# Root_ESP_v1_0.net
KiCad netlist of a schematic drawn in EAGLE
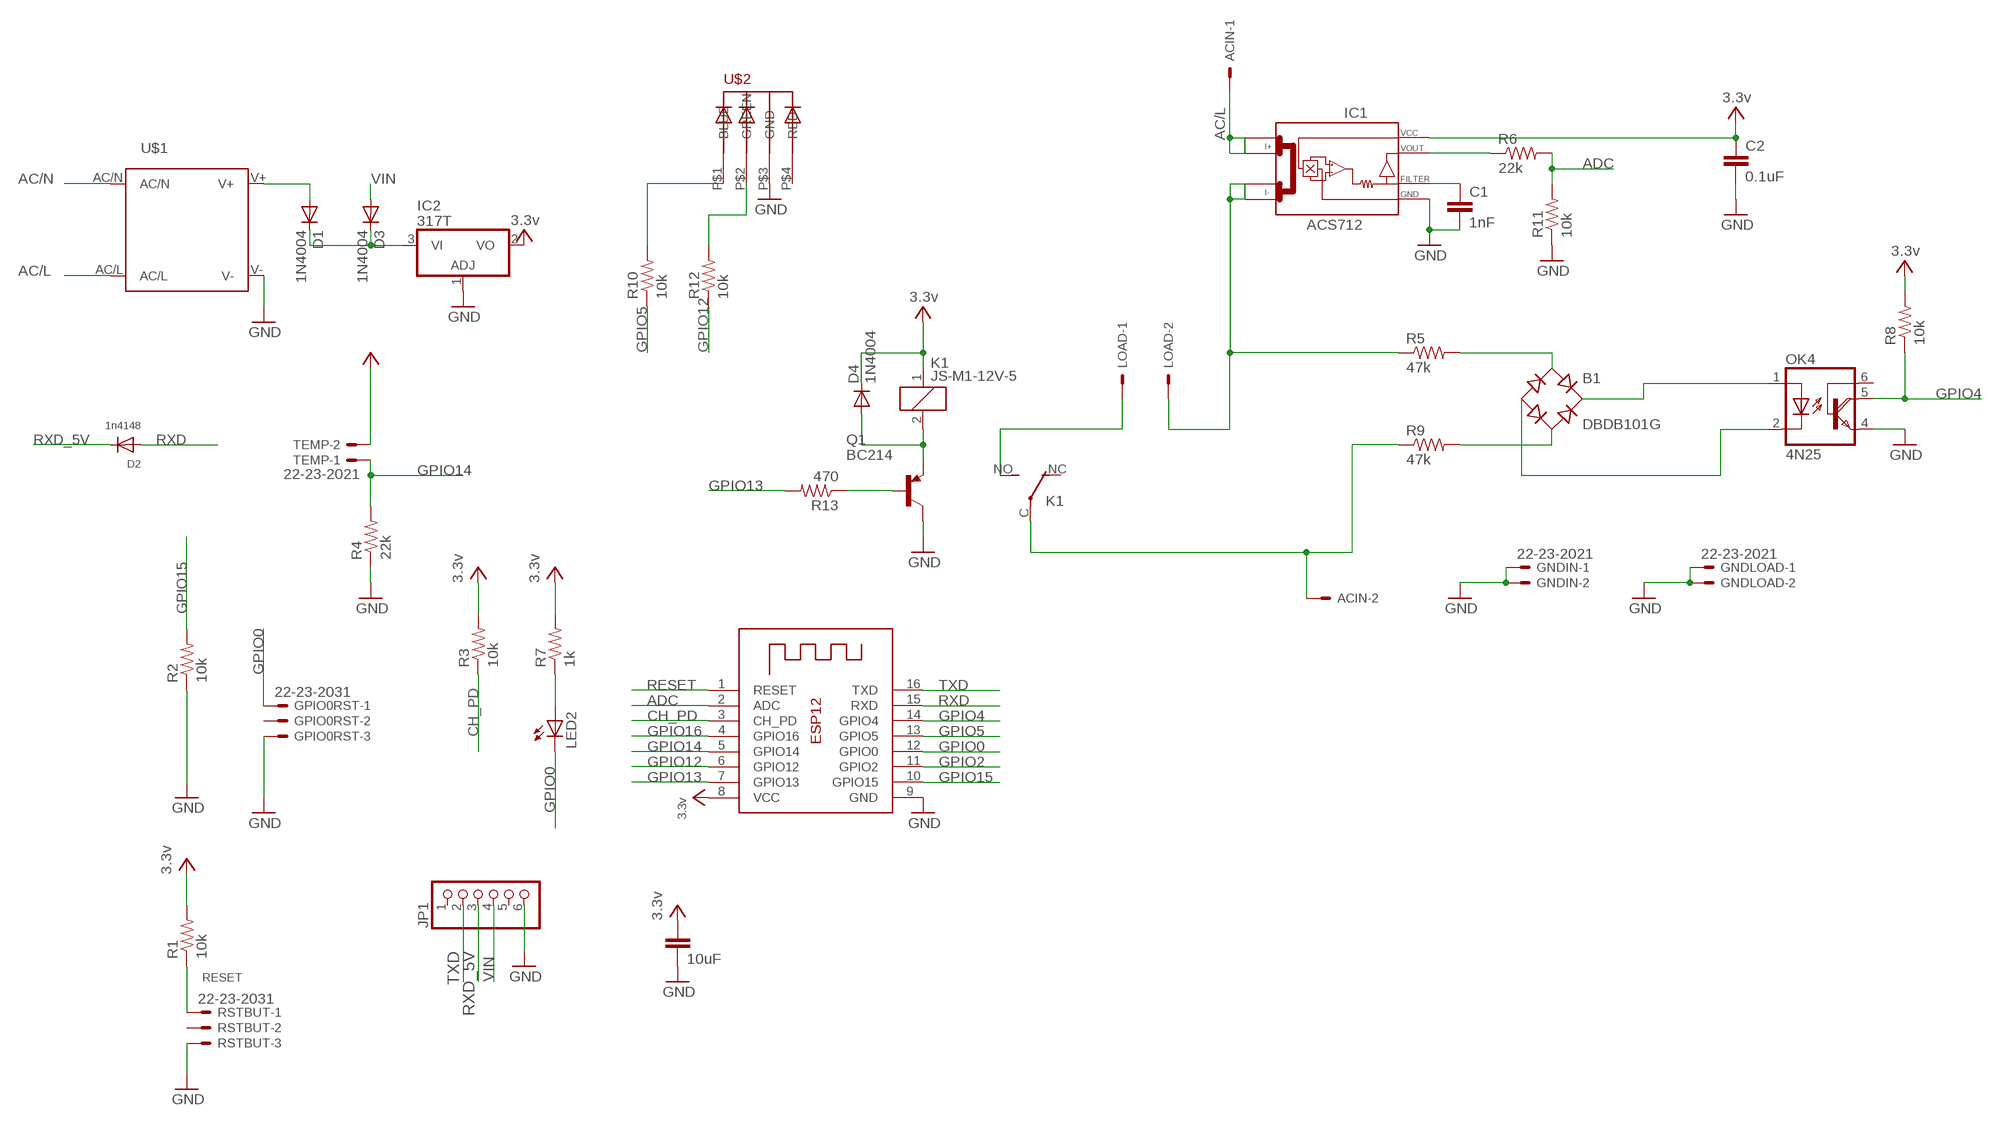
[diagram p0: schematic, sheet 1]

(export (version "E")
  (design (tool "Eeschema 10.0.6"))
  (components
    (comp (ref "ACIN")
      (value "22-23-2021")
      (footprint "eagle-import:22-23-2021")
      (fields (field (name "MF") "MOLEX"))
      (libsource (lib "eagle-import") (part "22-23-2021"))
    )
    (comp (ref "B1")
      (value "DBDB101G")
      (footprint "eagle-import:DB")
      (libsource (lib "eagle-import") (part "DB?GDB101"))
    )
    (comp (ref "C1")
      (value "1nF")
      (footprint "eagle-import:C5B2.5")
      (libsource (lib "eagle-import") (part "C5/2.5"))
    )
    (comp (ref "C2")
      (value "0.1uF")
      (footprint "eagle-import:C5B2.5")
      (libsource (lib "eagle-import") (part "C5/2.5"))
    )
    (comp (ref "C3")
      (value "10uF")
      (footprint "eagle-import:C5B3")
      (fields (field (name "C5") "0.1uF"))
      (libsource (lib "eagle-import") (part "C5/3"))
    )
    (comp (ref "D1")
      (value "1N4004")
      (footprint "eagle-import:DO41-10")
      (libsource (lib "eagle-import") (part "1N4004"))
    )
    (comp (ref "D2")
      (value "1n4148")
      (footprint "eagle-import:DO-1N4148")
      (libsource (lib "eagle-import") (part "DIODEDO-1N4148"))
    )
    (comp (ref "D3")
      (value "1N4004")
      (footprint "eagle-import:DO41-10")
      (libsource (lib "eagle-import") (part "1N4004"))
    )
    (comp (ref "D4")
      (value "1N4004")
      (footprint "eagle-import:DO41-10")
      (libsource (lib "eagle-import") (part "1N4004"))
    )
    (comp (ref "GNDIN")
      (value "22-23-2021")
      (footprint "eagle-import:22-23-2021")
      (fields (field (name "MF") "MOLEX"))
      (libsource (lib "eagle-import") (part "22-23-2021"))
    )
    (comp (ref "GNDLOAD")
      (value "22-23-2021")
      (footprint "eagle-import:22-23-2021")
      (fields (field (name "MF") "MOLEX"))
      (libsource (lib "eagle-import") (part "22-23-2021"))
    )
    (comp (ref "GPIO0RST")
      (value "22-23-2031")
      (footprint "eagle-import:22-23-2031")
      (fields (field (name "MF") "MOLEX"))
      (libsource (lib "eagle-import") (part "22-23-2031"))
    )
    (comp (ref "IC1")
      (value "ACS712")
      (footprint "eagle-import:SO08")
      (libsource (lib "eagle-import") (part "ACS712"))
    )
    (comp (ref "IC2")
      (value "317T")
      (footprint "eagle-import:TO220H")
      (libsource (lib "eagle-import") (part "317T"))
    )
    (comp (ref "JP1")
      (value "PINHD-1X6-3.5MM")
      (footprint "eagle-import:1X06-3.5MM")
      (libsource (lib "eagle-import") (part "PINHD-1X6-3.5MM"))
    )
    (comp (ref "K1")
      (value "JS-M1-12V-5")
      (footprint "eagle-import:JS-M")
      (fields (field (name "MF") "FARNELL") (field (name "MPN") "JSM1-12V-5"))
      (libsource (lib "eagle-import") (part "JS-M1-12V-5"))
    )
    (comp (ref "LED2")
      (value "LED5MM")
      (footprint "eagle-import:LED5MM")
      (libsource (lib "eagle-import") (part "LED5MM"))
    )
    (comp (ref "LOAD")
      (value "22-23-2021")
      (footprint "eagle-import:22-23-2021")
      (fields (field (name "MF") "MOLEX"))
      (libsource (lib "eagle-import") (part "22-23-2021"))
    )
    (comp (ref "OK4")
      (value "4N25")
      (footprint "eagle-import:DIL06")
      (libsource (lib "eagle-import") (part "4N25"))
    )
    (comp (ref "Q1")
      (value "BC214")
      (footprint "eagle-import:TO92")
      (libsource (lib "eagle-import") (part "BC214"))
    )
    (comp (ref "R1")
      (value "10k")
      (footprint "eagle-import:0204_7")
      (libsource (lib "eagle-import") (part "R-US_0204/7"))
    )
    (comp (ref "R2")
      (value "10k")
      (footprint "eagle-import:0204_7")
      (libsource (lib "eagle-import") (part "R-US_0204/7"))
    )
    (comp (ref "R3")
      (value "10k")
      (footprint "eagle-import:0204_7")
      (libsource (lib "eagle-import") (part "R-US_0204/7"))
    )
    (comp (ref "R4")
      (value "22k")
      (footprint "eagle-import:0204_7")
      (libsource (lib "eagle-import") (part "R-US_0204/7"))
    )
    (comp (ref "R5")
      (value "47k")
      (footprint "eagle-import:0204_7")
      (libsource (lib "eagle-import") (part "R-US_0204/7"))
    )
    (comp (ref "R6")
      (value "22k")
      (footprint "eagle-import:0204_7")
      (libsource (lib "eagle-import") (part "R-US_0204/7"))
    )
    (comp (ref "R7")
      (value "1k")
      (footprint "eagle-import:0204_7")
      (libsource (lib "eagle-import") (part "R-US_0204/7"))
    )
    (comp (ref "R8")
      (value "10k")
      (footprint "eagle-import:0204_7")
      (libsource (lib "eagle-import") (part "R-US_0204/7"))
    )
    (comp (ref "R9")
      (value "47k")
      (footprint "eagle-import:0204_7")
      (libsource (lib "eagle-import") (part "R-US_0204/7"))
    )
    (comp (ref "R10")
      (value "10k")
      (footprint "eagle-import:0204_7")
      (libsource (lib "eagle-import") (part "R-US_0204/7"))
    )
    (comp (ref "R11")
      (value "10k")
      (footprint "eagle-import:0204_7")
      (libsource (lib "eagle-import") (part "R-US_0204/7"))
    )
    (comp (ref "R12")
      (value "10k")
      (footprint "eagle-import:0204_7")
      (libsource (lib "eagle-import") (part "R-US_0204/7"))
    )
    (comp (ref "R13")
      (value "470")
      (footprint "eagle-import:0204_7")
      (libsource (lib "eagle-import") (part "R-US_0204/7"))
    )
    (comp (ref "RSTBUT")
      (value "22-23-2031")
      (footprint "eagle-import:22-23-2031")
      (fields (field (name "MF") "MOLEX"))
      (libsource (lib "eagle-import") (part "22-23-2031"))
    )
    (comp (ref "TEMP")
      (value "22-23-2021")
      (footprint "eagle-import:22-23-2021")
      (fields (field (name "MF") "MOLEX"))
      (libsource (lib "eagle-import") (part "22-23-2021"))
    )
    (comp (ref "U$1")
      (value "IRM_03IRM_03")
      (footprint "eagle-import:IRM_03")
      (libsource (lib "eagle-import") (part "IRM_03IRM_03"))
    )
    (comp (ref "U$2")
      (value "5MMRGBLED")
      (footprint "eagle-import:LED5MMRGB")
      (libsource (lib "eagle-import") (part "5MMRGBLED"))
    )
    (comp (ref "X1")
      (value "ESP-12")
      (footprint "eagle-import:ESP-12")
      (libsource (lib "eagle-import") (part "ESP-12"))
    )
  )
  (nets
    (net (code "1") (name "/AC{slash}L") (class "Default")
      (node (ref "ACIN") (pin "1") (pinfunction "S_1") (pintype "passive"))
      (node (ref "IC1") (pin "1") (pinfunction "I+_0_1") (pintype "bidirectional"))
      (node (ref "IC1") (pin "2") (pinfunction "I+_1_2") (pintype "bidirectional"))
      (node (ref "U$1") (pin "AC/L") (pinfunction "AC/L_AC/L") (pintype "input"))
    )
    (net (code "2") (name "/AC{slash}N") (class "Default")
      (node (ref "ACIN") (pin "2") (pinfunction "S_2") (pintype "passive"))
      (node (ref "K1") (pin "C") (pinfunction "P_C") (pintype "passive"))
      (node (ref "R9") (pin "1") (pinfunction "1_1") (pintype "passive"))
      (node (ref "U$1") (pin "AC/N") (pinfunction "AC/N_AC/N") (pintype "input"))
    )
    (net (code "3") (name "/ADC") (class "Default")
      (node (ref "R11") (pin "2") (pinfunction "2_2") (pintype "passive"))
      (node (ref "R6") (pin "2") (pinfunction "2_2") (pintype "passive"))
      (node (ref "X1") (pin "2") (pinfunction "ADC_2") (pintype "passive"))
    )
    (net (code "4") (name "/CH_PD") (class "Default")
      (node (ref "R3") (pin "1") (pinfunction "1_1") (pintype "passive"))
      (node (ref "X1") (pin "3") (pinfunction "CH_PD_3") (pintype "input"))
    )
    (net (code "5") (name "/GPIO0") (class "Default")
      (node (ref "GPIO0RST") (pin "1") (pinfunction "S_1") (pintype "passive"))
      (node (ref "LED2") (pin "K") (pinfunction "C_K") (pintype "passive"))
      (node (ref "X1") (pin "12") (pinfunction "GPIO0_12") (pintype "bidirectional"))
    )
    (net (code "6") (name "/GPIO2") (class "Default")
      (node (ref "X1") (pin "11") (pinfunction "GPIO2_11") (pintype "bidirectional"))
    )
    (net (code "7") (name "/GPIO4") (class "Default")
      (node (ref "OK4") (pin "5") (pinfunction "COL_5") (pintype "passive"))
      (node (ref "R8") (pin "1") (pinfunction "1_1") (pintype "passive"))
      (node (ref "X1") (pin "14") (pinfunction "GPIO4_14") (pintype "bidirectional"))
    )
    (net (code "8") (name "/GPIO5") (class "Default")
      (node (ref "R10") (pin "1") (pinfunction "1_1") (pintype "passive"))
      (node (ref "X1") (pin "13") (pinfunction "GPIO5_13") (pintype "bidirectional"))
    )
    (net (code "9") (name "/GPIO12") (class "Default")
      (node (ref "R12") (pin "1") (pinfunction "1_1") (pintype "passive"))
      (node (ref "X1") (pin "6") (pinfunction "GPIO12_6") (pintype "bidirectional"))
    )
    (net (code "10") (name "/GPIO13") (class "Default")
      (node (ref "R13") (pin "2") (pinfunction "2_2") (pintype "passive"))
      (node (ref "X1") (pin "7") (pinfunction "GPIO13_7") (pintype "bidirectional"))
    )
    (net (code "11") (name "/GPIO14") (class "Default")
      (node (ref "R4") (pin "2") (pinfunction "2_2") (pintype "passive"))
      (node (ref "TEMP") (pin "1") (pinfunction "S_1") (pintype "passive"))
      (node (ref "X1") (pin "5") (pinfunction "GPIO14_5") (pintype "bidirectional"))
    )
    (net (code "12") (name "/GPIO15") (class "Default")
      (node (ref "R2") (pin "2") (pinfunction "2_2") (pintype "passive"))
      (node (ref "X1") (pin "10") (pinfunction "GPIO15_10") (pintype "bidirectional"))
    )
    (net (code "13") (name "/GPIO16") (class "Default")
      (node (ref "X1") (pin "4") (pinfunction "GPIO16_4") (pintype "bidirectional"))
    )
    (net (code "14") (name "/RESET") (class "Default")
      (node (ref "R1") (pin "1") (pinfunction "1_1") (pintype "passive"))
      (node (ref "RSTBUT") (pin "1") (pinfunction "S_1") (pintype "passive"))
      (node (ref "X1") (pin "1") (pinfunction "RESET_1") (pintype "input"))
    )
    (net (code "15") (name "/RXD") (class "Default")
      (node (ref "D2") (pin "A") (pinfunction "A_A") (pintype "passive"))
      (node (ref "X1") (pin "15") (pinfunction "RXD_15") (pintype "input"))
    )
    (net (code "16") (name "/RXD_5V") (class "Default")
      (node (ref "D2") (pin "C") (pinfunction "C_C") (pintype "passive"))
      (node (ref "JP1") (pin "3") (pinfunction "3_3") (pintype "passive"))
    )
    (net (code "17") (name "/TXD") (class "Default")
      (node (ref "JP1") (pin "2") (pinfunction "2_2") (pintype "passive"))
      (node (ref "X1") (pin "16") (pinfunction "TXD_16") (pintype "output"))
    )
    (net (code "18") (name "/VIN") (class "Default")
      (node (ref "D3") (pin "A") (pinfunction "A_A") (pintype "passive"))
      (node (ref "JP1") (pin "4") (pinfunction "4_4") (pintype "passive"))
    )
    (net (code "19") (name "3.3v") (class "Default")
      (node (ref "C2") (pin "1") (pinfunction "1_1") (pintype "passive"))
      (node (ref "C3") (pin "1") (pinfunction "1_1") (pintype "passive"))
      (node (ref "D4") (pin "C") (pinfunction "C_C") (pintype "passive"))
      (node (ref "IC1") (pin "8") (pinfunction "VCC_8") (pintype "power_in"))
      (node (ref "IC2") (pin "2") (pinfunction "VO_2") (pintype "passive"))
      (node (ref "K1") (pin "1") (pinfunction "1_1") (pintype "passive"))
      (node (ref "R1") (pin "2") (pinfunction "2_2") (pintype "passive"))
      (node (ref "R3") (pin "2") (pinfunction "2_2") (pintype "passive"))
      (node (ref "R7") (pin "2") (pinfunction "2_2") (pintype "passive"))
      (node (ref "R8") (pin "2") (pinfunction "2_2") (pintype "passive"))
      (node (ref "TEMP") (pin "2") (pinfunction "S_2") (pintype "passive"))
      (node (ref "X1") (pin "8") (pinfunction "VCC_8") (pintype "power_in"))
    )
    (net (code "20") (name "GND") (class "Default")
      (node (ref "C1") (pin "2") (pinfunction "2_2") (pintype "passive"))
      (node (ref "C2") (pin "2") (pinfunction "2_2") (pintype "passive"))
      (node (ref "C3") (pin "2") (pinfunction "2_2") (pintype "passive"))
      (node (ref "GNDIN") (pin "1") (pinfunction "S_1") (pintype "passive"))
      (node (ref "GNDIN") (pin "2") (pinfunction "S_2") (pintype "passive"))
      (node (ref "GNDLOAD") (pin "1") (pinfunction "S_1") (pintype "passive"))
      (node (ref "GNDLOAD") (pin "2") (pinfunction "S_2") (pintype "passive"))
      (node (ref "GPIO0RST") (pin "3") (pinfunction "S_3") (pintype "passive"))
      (node (ref "IC1") (pin "5") (pinfunction "GND_5") (pintype "power_in"))
      (node (ref "IC2") (pin "1") (pinfunction "ADJ_1") (pintype "input"))
      (node (ref "JP1") (pin "6") (pinfunction "6_6") (pintype "passive"))
      (node (ref "OK4") (pin "4") (pinfunction "E_4") (pintype "passive"))
      (node (ref "Q1") (pin "3") (pinfunction "C_3") (pintype "passive"))
      (node (ref "R11") (pin "1") (pinfunction "1_1") (pintype "passive"))
      (node (ref "R2") (pin "1") (pinfunction "1_1") (pintype "passive"))
      (node (ref "R4") (pin "1") (pinfunction "1_1") (pintype "passive"))
      (node (ref "RSTBUT") (pin "3") (pinfunction "S_3") (pintype "passive"))
      (node (ref "U$1") (pin "V-") (pinfunction "V-_V-") (pintype "output"))
      (node (ref "U$2") (pin "P$3") (pinfunction "GND_P$3") (pintype "bidirectional"))
      (node (ref "X1") (pin "9") (pinfunction "GND_9") (pintype "power_in"))
    )
    (net (code "21") (name "Net-(B1-PadAC1)") (class "Default")
      (node (ref "B1") (pin "AC1") (pinfunction "AC1_AC1") (pintype "passive"))
      (node (ref "R5") (pin "2") (pinfunction "2_2") (pintype "passive"))
    )
    (net (code "22") (name "Net-(B1-PadAC2)") (class "Default")
      (node (ref "B1") (pin "AC2") (pinfunction "AC2_AC2") (pintype "passive"))
      (node (ref "R9") (pin "2") (pinfunction "2_2") (pintype "passive"))
    )
    (net (code "23") (name "Net-(D1-PadA)") (class "Default")
      (node (ref "D1") (pin "A") (pinfunction "A_A") (pintype "passive"))
      (node (ref "U$1") (pin "V+") (pinfunction "V+_V+") (pintype "output"))
    )
    (net (code "24") (name "Net-(IC1-FILTER)") (class "Default")
      (node (ref "C1") (pin "1") (pinfunction "1_1") (pintype "passive"))
      (node (ref "IC1") (pin "6") (pinfunction "FILTER_6") (pintype "bidirectional"))
    )
    (net (code "25") (name "Net-(IC1-I-_0)") (class "Default")
      (node (ref "IC1") (pin "3") (pinfunction "I-_0_3") (pintype "bidirectional"))
      (node (ref "IC1") (pin "4") (pinfunction "I-_1_4") (pintype "bidirectional"))
      (node (ref "LOAD") (pin "2") (pinfunction "S_2") (pintype "passive"))
      (node (ref "R5") (pin "1") (pinfunction "1_1") (pintype "passive"))
    )
    (net (code "26") (name "Net-(IC1-VOUT)") (class "Default")
      (node (ref "IC1") (pin "7") (pinfunction "VOUT_7") (pintype "output"))
      (node (ref "R6") (pin "1") (pinfunction "1_1") (pintype "passive"))
    )
    (net (code "27") (name "Net-(IC2-VI)") (class "Default")
      (node (ref "D1") (pin "C") (pinfunction "C_C") (pintype "passive"))
      (node (ref "D3") (pin "C") (pinfunction "C_C") (pintype "passive"))
      (node (ref "IC2") (pin "3") (pinfunction "VI_3") (pintype "input"))
    )
    (net (code "28") (name "Net-(K1B-S)") (class "Default")
      (node (ref "K1") (pin "NO") (pinfunction "S_NO") (pintype "passive"))
      (node (ref "LOAD") (pin "1") (pinfunction "S_1") (pintype "passive"))
    )
    (net (code "29") (name "Net-(LED2-PadA)") (class "Default")
      (node (ref "LED2") (pin "A") (pinfunction "A_A") (pintype "passive"))
      (node (ref "R7") (pin "1") (pinfunction "1_1") (pintype "passive"))
    )
    (net (code "30") (name "Net-(OK4-A)") (class "Default")
      (node (ref "B1") (pin "+") (pinfunction "+_+") (pintype "passive"))
      (node (ref "OK4") (pin "1") (pinfunction "A_1") (pintype "passive"))
    )
    (net (code "31") (name "Net-(OK4-C)") (class "Default")
      (node (ref "B1") (pin "-") (pinfunction "-_-") (pintype "passive"))
      (node (ref "OK4") (pin "2") (pinfunction "C_2") (pintype "passive"))
    )
    (net (code "32") (name "Net-(Q1-B)") (class "Default")
      (node (ref "Q1") (pin "2") (pinfunction "B_2") (pintype "passive"))
      (node (ref "R13") (pin "1") (pinfunction "1_1") (pintype "passive"))
    )
    (net (code "33") (name "Net-(Q1-E)") (class "Default")
      (node (ref "D4") (pin "A") (pinfunction "A_A") (pintype "passive"))
      (node (ref "K1") (pin "2") (pinfunction "2_2") (pintype "passive"))
      (node (ref "Q1") (pin "1") (pinfunction "E_1") (pintype "passive"))
    )
    (net (code "34") (name "Net-(U$2-BLUE)") (class "Default")
      (node (ref "R10") (pin "2") (pinfunction "2_2") (pintype "passive"))
      (node (ref "U$2") (pin "P$1") (pinfunction "BLUE_P$1") (pintype "bidirectional"))
    )
    (net (code "35") (name "Net-(U$2-GREEN)") (class "Default")
      (node (ref "R12") (pin "2") (pinfunction "2_2") (pintype "passive"))
      (node (ref "U$2") (pin "P$2") (pinfunction "GREEN_P$2") (pintype "bidirectional"))
    )
    (net (code "36") (name "unconnected-(GPIO0RSTB-S-Pad2)") (class "Default")
      (node (ref "GPIO0RST") (pin "2") (pinfunction "S_2") (pintype "passive"))
    )
    (net (code "37") (name "unconnected-(JP1-Pad1)") (class "Default")
      (node (ref "JP1") (pin "1") (pinfunction "1_1") (pintype "passive"))
    )
    (net (code "38") (name "unconnected-(JP1-Pad5)") (class "Default")
      (node (ref "JP1") (pin "5") (pinfunction "5_5") (pintype "passive"))
    )
    (net (code "39") (name "unconnected-(K1B-O-PadNC)") (class "Default")
      (node (ref "K1") (pin "NC") (pinfunction "O_NC") (pintype "passive"))
    )
    (net (code "40") (name "unconnected-(OK4-B-Pad6)") (class "Default")
      (node (ref "OK4") (pin "6") (pinfunction "B_6") (pintype "passive"))
    )
    (net (code "41") (name "unconnected-(RSTBUTB-S-Pad2)") (class "Default")
      (node (ref "RSTBUT") (pin "2") (pinfunction "S_2") (pintype "passive"))
    )
    (net (code "42") (name "unconnected-(U$2-RED-PadP$4)") (class "Default")
      (node (ref "U$2") (pin "P$4") (pinfunction "RED_P$4") (pintype "bidirectional"))
    )
  )
)
